# 01-LED.net
KiCad netlist of a schematic drawn in Altium Designer
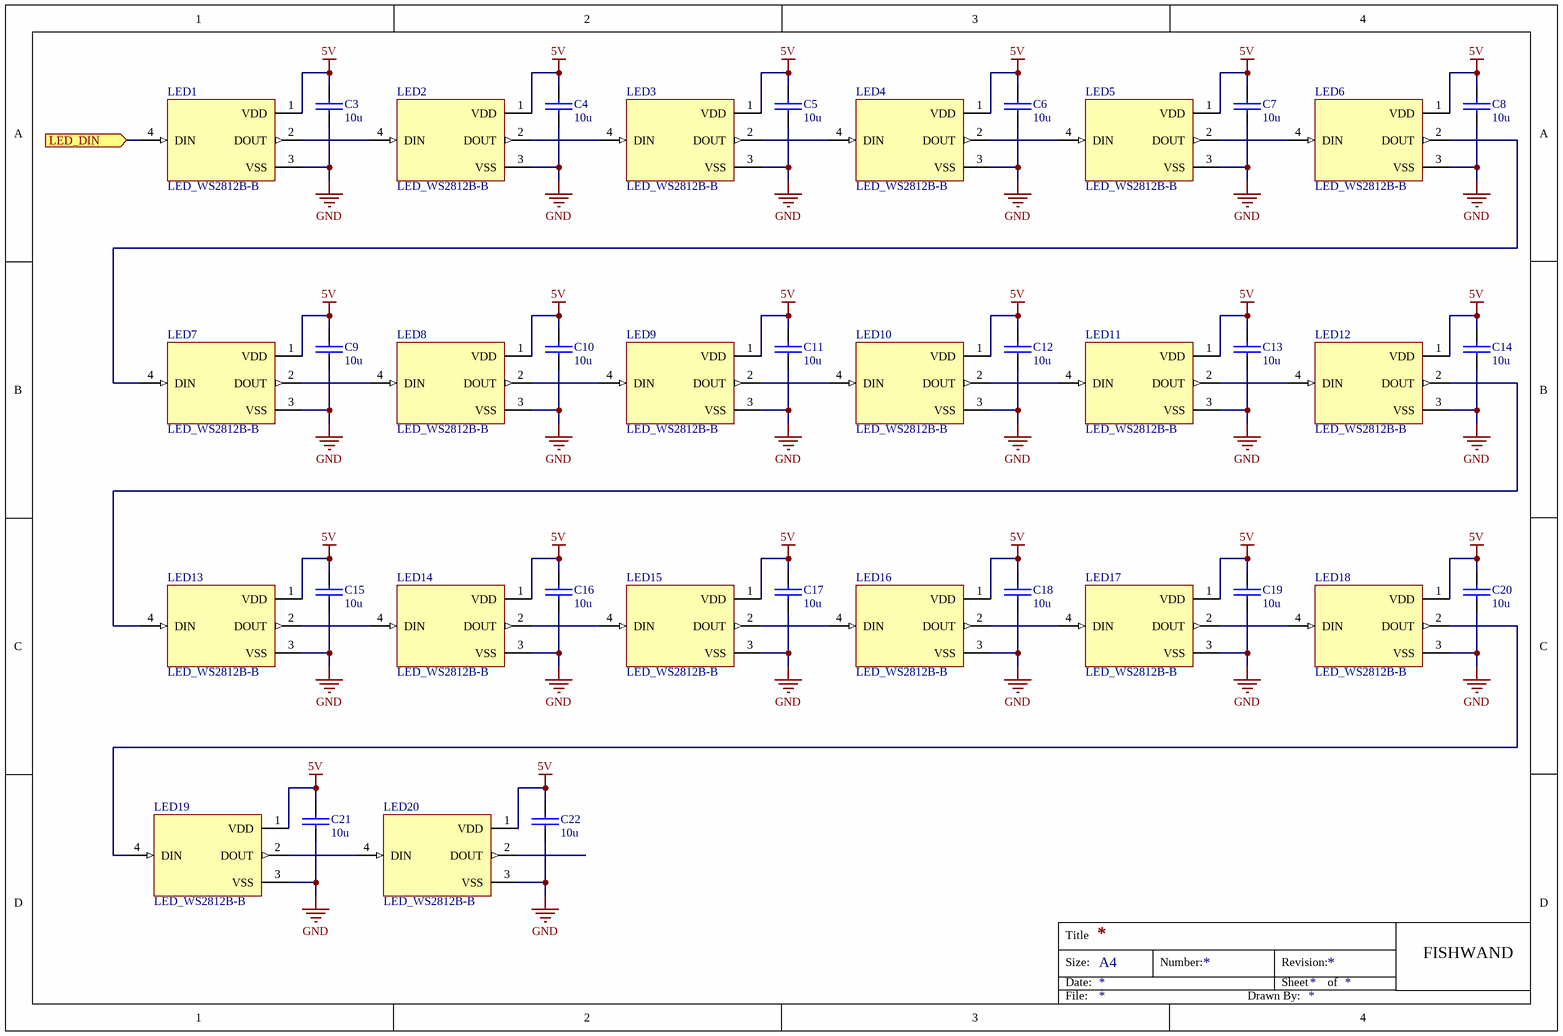
[diagram p0: 01-LED.SchDoc]

(export (version "E")
  (design (tool "Eeschema 10.0.6"))
  (components
    (comp (ref "C3")
      (value "10u")
      (footprint "CAPC100X50X65")
      (description "CAP CER 10UF 10V X5R 0402")
      (fields (field (name "MANUFACTURER") "Samsung Electro-Mechanics"))
      (libsource (lib "FishWand_Schlib") (part "C_10UF_10V_X5R_0402"))
    )
    (comp (ref "C4")
      (value "10u")
      (footprint "CAPC100X50X65")
      (description "CAP CER 10UF 10V X5R 0402")
      (fields (field (name "MANUFACTURER") "Samsung Electro-Mechanics"))
      (libsource (lib "FishWand_Schlib") (part "C_10UF_10V_X5R_0402"))
    )
    (comp (ref "C5")
      (value "10u")
      (footprint "CAPC100X50X65")
      (description "CAP CER 10UF 10V X5R 0402")
      (fields (field (name "MANUFACTURER") "Samsung Electro-Mechanics"))
      (libsource (lib "FishWand_Schlib") (part "C_10UF_10V_X5R_0402"))
    )
    (comp (ref "C6")
      (value "10u")
      (footprint "CAPC100X50X65")
      (description "CAP CER 10UF 10V X5R 0402")
      (fields (field (name "MANUFACTURER") "Samsung Electro-Mechanics"))
      (libsource (lib "FishWand_Schlib") (part "C_10UF_10V_X5R_0402"))
    )
    (comp (ref "C7")
      (value "10u")
      (footprint "CAPC100X50X65")
      (description "CAP CER 10UF 10V X5R 0402")
      (fields (field (name "MANUFACTURER") "Samsung Electro-Mechanics"))
      (libsource (lib "FishWand_Schlib") (part "C_10UF_10V_X5R_0402"))
    )
    (comp (ref "C8")
      (value "10u")
      (footprint "CAPC100X50X65")
      (description "CAP CER 10UF 10V X5R 0402")
      (fields (field (name "MANUFACTURER") "Samsung Electro-Mechanics"))
      (libsource (lib "FishWand_Schlib") (part "C_10UF_10V_X5R_0402"))
    )
    (comp (ref "C9")
      (value "10u")
      (footprint "CAPC100X50X65")
      (description "CAP CER 10UF 10V X5R 0402")
      (fields (field (name "MANUFACTURER") "Samsung Electro-Mechanics"))
      (libsource (lib "FishWand_Schlib") (part "C_10UF_10V_X5R_0402"))
    )
    (comp (ref "C10")
      (value "10u")
      (footprint "CAPC100X50X65")
      (description "CAP CER 10UF 10V X5R 0402")
      (fields (field (name "MANUFACTURER") "Samsung Electro-Mechanics"))
      (libsource (lib "FishWand_Schlib") (part "C_10UF_10V_X5R_0402"))
    )
    (comp (ref "C11")
      (value "10u")
      (footprint "CAPC100X50X65")
      (description "CAP CER 10UF 10V X5R 0402")
      (fields (field (name "MANUFACTURER") "Samsung Electro-Mechanics"))
      (libsource (lib "FishWand_Schlib") (part "C_10UF_10V_X5R_0402"))
    )
    (comp (ref "C12")
      (value "10u")
      (footprint "CAPC100X50X65")
      (description "CAP CER 10UF 10V X5R 0402")
      (fields (field (name "MANUFACTURER") "Samsung Electro-Mechanics"))
      (libsource (lib "FishWand_Schlib") (part "C_10UF_10V_X5R_0402"))
    )
    (comp (ref "C13")
      (value "10u")
      (footprint "CAPC100X50X65")
      (description "CAP CER 10UF 10V X5R 0402")
      (fields (field (name "MANUFACTURER") "Samsung Electro-Mechanics"))
      (libsource (lib "FishWand_Schlib") (part "C_10UF_10V_X5R_0402"))
    )
    (comp (ref "C14")
      (value "10u")
      (footprint "CAPC100X50X65")
      (description "CAP CER 10UF 10V X5R 0402")
      (fields (field (name "MANUFACTURER") "Samsung Electro-Mechanics"))
      (libsource (lib "FishWand_Schlib") (part "C_10UF_10V_X5R_0402"))
    )
    (comp (ref "C15")
      (value "10u")
      (footprint "CAPC100X50X65")
      (description "CAP CER 10UF 10V X5R 0402")
      (fields (field (name "MANUFACTURER") "Samsung Electro-Mechanics"))
      (libsource (lib "FishWand_Schlib") (part "C_10UF_10V_X5R_0402"))
    )
    (comp (ref "C16")
      (value "10u")
      (footprint "CAPC100X50X65")
      (description "CAP CER 10UF 10V X5R 0402")
      (fields (field (name "MANUFACTURER") "Samsung Electro-Mechanics"))
      (libsource (lib "FishWand_Schlib") (part "C_10UF_10V_X5R_0402"))
    )
    (comp (ref "C17")
      (value "10u")
      (footprint "CAPC100X50X65")
      (description "CAP CER 10UF 10V X5R 0402")
      (fields (field (name "MANUFACTURER") "Samsung Electro-Mechanics"))
      (libsource (lib "FishWand_Schlib") (part "C_10UF_10V_X5R_0402"))
    )
    (comp (ref "C18")
      (value "10u")
      (footprint "CAPC100X50X65")
      (description "CAP CER 10UF 10V X5R 0402")
      (fields (field (name "MANUFACTURER") "Samsung Electro-Mechanics"))
      (libsource (lib "FishWand_Schlib") (part "C_10UF_10V_X5R_0402"))
    )
    (comp (ref "C19")
      (value "10u")
      (footprint "CAPC100X50X65")
      (description "CAP CER 10UF 10V X5R 0402")
      (fields (field (name "MANUFACTURER") "Samsung Electro-Mechanics"))
      (libsource (lib "FishWand_Schlib") (part "C_10UF_10V_X5R_0402"))
    )
    (comp (ref "C20")
      (value "10u")
      (footprint "CAPC100X50X65")
      (description "CAP CER 10UF 10V X5R 0402")
      (fields (field (name "MANUFACTURER") "Samsung Electro-Mechanics"))
      (libsource (lib "FishWand_Schlib") (part "C_10UF_10V_X5R_0402"))
    )
    (comp (ref "C21")
      (value "10u")
      (footprint "CAPC100X50X65")
      (description "CAP CER 10UF 10V X5R 0402")
      (fields (field (name "MANUFACTURER") "Samsung Electro-Mechanics"))
      (libsource (lib "FishWand_Schlib") (part "C_10UF_10V_X5R_0402"))
    )
    (comp (ref "C22")
      (value "10u")
      (footprint "CAPC100X50X65")
      (description "CAP CER 10UF 10V X5R 0402")
      (fields (field (name "MANUFACTURER") "Samsung Electro-Mechanics"))
      (libsource (lib "FishWand_Schlib") (part "C_10UF_10V_X5R_0402"))
    )
    (comp (ref "LED1")
      (value "LED_WS2812B-B")
      (footprint "LED_WS2812B-B")
      (description "Intelligent control LED integrated light source")
      (fields (field (name "MANUFACTURER") "Worldsemi"))
      (libsource (lib "FishWand_Schlib") (part "LED_WS2812B-B"))
    )
    (comp (ref "LED2")
      (value "LED_WS2812B-B")
      (footprint "LED_WS2812B-B")
      (description "Intelligent control LED integrated light source")
      (fields (field (name "MANUFACTURER") "Worldsemi"))
      (libsource (lib "FishWand_Schlib") (part "LED_WS2812B-B"))
    )
    (comp (ref "LED3")
      (value "LED_WS2812B-B")
      (footprint "LED_WS2812B-B")
      (description "Intelligent control LED integrated light source")
      (fields (field (name "MANUFACTURER") "Worldsemi"))
      (libsource (lib "FishWand_Schlib") (part "LED_WS2812B-B"))
    )
    (comp (ref "LED4")
      (value "LED_WS2812B-B")
      (footprint "LED_WS2812B-B")
      (description "Intelligent control LED integrated light source")
      (fields (field (name "MANUFACTURER") "Worldsemi"))
      (libsource (lib "FishWand_Schlib") (part "LED_WS2812B-B"))
    )
    (comp (ref "LED5")
      (value "LED_WS2812B-B")
      (footprint "LED_WS2812B-B")
      (description "Intelligent control LED integrated light source")
      (fields (field (name "MANUFACTURER") "Worldsemi"))
      (libsource (lib "FishWand_Schlib") (part "LED_WS2812B-B"))
    )
    (comp (ref "LED6")
      (value "LED_WS2812B-B")
      (footprint "LED_WS2812B-B")
      (description "Intelligent control LED integrated light source")
      (fields (field (name "MANUFACTURER") "Worldsemi"))
      (libsource (lib "FishWand_Schlib") (part "LED_WS2812B-B"))
    )
    (comp (ref "LED7")
      (value "LED_WS2812B-B")
      (footprint "LED_WS2812B-B")
      (description "Intelligent control LED integrated light source")
      (fields (field (name "MANUFACTURER") "Worldsemi"))
      (libsource (lib "FishWand_Schlib") (part "LED_WS2812B-B"))
    )
    (comp (ref "LED8")
      (value "LED_WS2812B-B")
      (footprint "LED_WS2812B-B")
      (description "Intelligent control LED integrated light source")
      (fields (field (name "MANUFACTURER") "Worldsemi"))
      (libsource (lib "FishWand_Schlib") (part "LED_WS2812B-B"))
    )
    (comp (ref "LED9")
      (value "LED_WS2812B-B")
      (footprint "LED_WS2812B-B")
      (description "Intelligent control LED integrated light source")
      (fields (field (name "MANUFACTURER") "Worldsemi"))
      (libsource (lib "FishWand_Schlib") (part "LED_WS2812B-B"))
    )
    (comp (ref "LED10")
      (value "LED_WS2812B-B")
      (footprint "LED_WS2812B-B")
      (description "Intelligent control LED integrated light source")
      (fields (field (name "MANUFACTURER") "Worldsemi"))
      (libsource (lib "FishWand_Schlib") (part "LED_WS2812B-B"))
    )
    (comp (ref "LED11")
      (value "LED_WS2812B-B")
      (footprint "LED_WS2812B-B")
      (description "Intelligent control LED integrated light source")
      (fields (field (name "MANUFACTURER") "Worldsemi"))
      (libsource (lib "FishWand_Schlib") (part "LED_WS2812B-B"))
    )
    (comp (ref "LED12")
      (value "LED_WS2812B-B")
      (footprint "LED_WS2812B-B")
      (description "Intelligent control LED integrated light source")
      (fields (field (name "MANUFACTURER") "Worldsemi"))
      (libsource (lib "FishWand_Schlib") (part "LED_WS2812B-B"))
    )
    (comp (ref "LED13")
      (value "LED_WS2812B-B")
      (footprint "LED_WS2812B-B")
      (description "Intelligent control LED integrated light source")
      (fields (field (name "MANUFACTURER") "Worldsemi"))
      (libsource (lib "FishWand_Schlib") (part "LED_WS2812B-B"))
    )
    (comp (ref "LED14")
      (value "LED_WS2812B-B")
      (footprint "LED_WS2812B-B")
      (description "Intelligent control LED integrated light source")
      (fields (field (name "MANUFACTURER") "Worldsemi"))
      (libsource (lib "FishWand_Schlib") (part "LED_WS2812B-B"))
    )
    (comp (ref "LED15")
      (value "LED_WS2812B-B")
      (footprint "LED_WS2812B-B")
      (description "Intelligent control LED integrated light source")
      (fields (field (name "MANUFACTURER") "Worldsemi"))
      (libsource (lib "FishWand_Schlib") (part "LED_WS2812B-B"))
    )
    (comp (ref "LED16")
      (value "LED_WS2812B-B")
      (footprint "LED_WS2812B-B")
      (description "Intelligent control LED integrated light source")
      (fields (field (name "MANUFACTURER") "Worldsemi"))
      (libsource (lib "FishWand_Schlib") (part "LED_WS2812B-B"))
    )
    (comp (ref "LED17")
      (value "LED_WS2812B-B")
      (footprint "LED_WS2812B-B")
      (description "Intelligent control LED integrated light source")
      (fields (field (name "MANUFACTURER") "Worldsemi"))
      (libsource (lib "FishWand_Schlib") (part "LED_WS2812B-B"))
    )
    (comp (ref "LED18")
      (value "LED_WS2812B-B")
      (footprint "LED_WS2812B-B")
      (description "Intelligent control LED integrated light source")
      (fields (field (name "MANUFACTURER") "Worldsemi"))
      (libsource (lib "FishWand_Schlib") (part "LED_WS2812B-B"))
    )
    (comp (ref "LED19")
      (value "LED_WS2812B-B")
      (footprint "LED_WS2812B-B")
      (description "Intelligent control LED integrated light source")
      (fields (field (name "MANUFACTURER") "Worldsemi"))
      (libsource (lib "FishWand_Schlib") (part "LED_WS2812B-B"))
    )
    (comp (ref "LED20")
      (value "LED_WS2812B-B")
      (footprint "LED_WS2812B-B")
      (description "Intelligent control LED integrated light source")
      (fields (field (name "MANUFACTURER") "Worldsemi"))
      (libsource (lib "FishWand_Schlib") (part "LED_WS2812B-B"))
    )
  )
  (nets
    (net (code "1") (name "/LED_DIN") (class "Default")
      (node (ref "LED1") (pin "4") (pinfunction "DIN_4") (pintype "input"))
    )
    (net (code "2") (name "5V") (class "Default")
      (node (ref "C10") (pin "1") (pinfunction "1_1") (pintype "passive"))
      (node (ref "C11") (pin "1") (pinfunction "1_1") (pintype "passive"))
      (node (ref "C12") (pin "1") (pinfunction "1_1") (pintype "passive"))
      (node (ref "C13") (pin "1") (pinfunction "1_1") (pintype "passive"))
      (node (ref "C14") (pin "1") (pinfunction "1_1") (pintype "passive"))
      (node (ref "C15") (pin "1") (pinfunction "1_1") (pintype "passive"))
      (node (ref "C16") (pin "1") (pinfunction "1_1") (pintype "passive"))
      (node (ref "C17") (pin "1") (pinfunction "1_1") (pintype "passive"))
      (node (ref "C18") (pin "1") (pinfunction "1_1") (pintype "passive"))
      (node (ref "C19") (pin "1") (pinfunction "1_1") (pintype "passive"))
      (node (ref "C20") (pin "1") (pinfunction "1_1") (pintype "passive"))
      (node (ref "C21") (pin "1") (pinfunction "1_1") (pintype "passive"))
      (node (ref "C22") (pin "1") (pinfunction "1_1") (pintype "passive"))
      (node (ref "C3") (pin "1") (pinfunction "1_1") (pintype "passive"))
      (node (ref "C4") (pin "1") (pinfunction "1_1") (pintype "passive"))
      (node (ref "C5") (pin "1") (pinfunction "1_1") (pintype "passive"))
      (node (ref "C6") (pin "1") (pinfunction "1_1") (pintype "passive"))
      (node (ref "C7") (pin "1") (pinfunction "1_1") (pintype "passive"))
      (node (ref "C8") (pin "1") (pinfunction "1_1") (pintype "passive"))
      (node (ref "C9") (pin "1") (pinfunction "1_1") (pintype "passive"))
      (node (ref "LED1") (pin "1") (pinfunction "VDD_1") (pintype "power_in"))
      (node (ref "LED10") (pin "1") (pinfunction "VDD_1") (pintype "power_in"))
      (node (ref "LED11") (pin "1") (pinfunction "VDD_1") (pintype "power_in"))
      (node (ref "LED12") (pin "1") (pinfunction "VDD_1") (pintype "power_in"))
      (node (ref "LED13") (pin "1") (pinfunction "VDD_1") (pintype "power_in"))
      (node (ref "LED14") (pin "1") (pinfunction "VDD_1") (pintype "power_in"))
      (node (ref "LED15") (pin "1") (pinfunction "VDD_1") (pintype "power_in"))
      (node (ref "LED16") (pin "1") (pinfunction "VDD_1") (pintype "power_in"))
      (node (ref "LED17") (pin "1") (pinfunction "VDD_1") (pintype "power_in"))
      (node (ref "LED18") (pin "1") (pinfunction "VDD_1") (pintype "power_in"))
      (node (ref "LED19") (pin "1") (pinfunction "VDD_1") (pintype "power_in"))
      (node (ref "LED2") (pin "1") (pinfunction "VDD_1") (pintype "power_in"))
      (node (ref "LED20") (pin "1") (pinfunction "VDD_1") (pintype "power_in"))
      (node (ref "LED3") (pin "1") (pinfunction "VDD_1") (pintype "power_in"))
      (node (ref "LED4") (pin "1") (pinfunction "VDD_1") (pintype "power_in"))
      (node (ref "LED5") (pin "1") (pinfunction "VDD_1") (pintype "power_in"))
      (node (ref "LED6") (pin "1") (pinfunction "VDD_1") (pintype "power_in"))
      (node (ref "LED7") (pin "1") (pinfunction "VDD_1") (pintype "power_in"))
      (node (ref "LED8") (pin "1") (pinfunction "VDD_1") (pintype "power_in"))
      (node (ref "LED9") (pin "1") (pinfunction "VDD_1") (pintype "power_in"))
    )
    (net (code "3") (name "GND") (class "Default")
      (node (ref "C10") (pin "2") (pinfunction "2_2") (pintype "passive"))
      (node (ref "C11") (pin "2") (pinfunction "2_2") (pintype "passive"))
      (node (ref "C12") (pin "2") (pinfunction "2_2") (pintype "passive"))
      (node (ref "C13") (pin "2") (pinfunction "2_2") (pintype "passive"))
      (node (ref "C14") (pin "2") (pinfunction "2_2") (pintype "passive"))
      (node (ref "C15") (pin "2") (pinfunction "2_2") (pintype "passive"))
      (node (ref "C16") (pin "2") (pinfunction "2_2") (pintype "passive"))
      (node (ref "C17") (pin "2") (pinfunction "2_2") (pintype "passive"))
      (node (ref "C18") (pin "2") (pinfunction "2_2") (pintype "passive"))
      (node (ref "C19") (pin "2") (pinfunction "2_2") (pintype "passive"))
      (node (ref "C20") (pin "2") (pinfunction "2_2") (pintype "passive"))
      (node (ref "C21") (pin "2") (pinfunction "2_2") (pintype "passive"))
      (node (ref "C22") (pin "2") (pinfunction "2_2") (pintype "passive"))
      (node (ref "C3") (pin "2") (pinfunction "2_2") (pintype "passive"))
      (node (ref "C4") (pin "2") (pinfunction "2_2") (pintype "passive"))
      (node (ref "C5") (pin "2") (pinfunction "2_2") (pintype "passive"))
      (node (ref "C6") (pin "2") (pinfunction "2_2") (pintype "passive"))
      (node (ref "C7") (pin "2") (pinfunction "2_2") (pintype "passive"))
      (node (ref "C8") (pin "2") (pinfunction "2_2") (pintype "passive"))
      (node (ref "C9") (pin "2") (pinfunction "2_2") (pintype "passive"))
      (node (ref "LED1") (pin "3") (pinfunction "VSS_3") (pintype "power_in"))
      (node (ref "LED10") (pin "3") (pinfunction "VSS_3") (pintype "power_in"))
      (node (ref "LED11") (pin "3") (pinfunction "VSS_3") (pintype "power_in"))
      (node (ref "LED12") (pin "3") (pinfunction "VSS_3") (pintype "power_in"))
      (node (ref "LED13") (pin "3") (pinfunction "VSS_3") (pintype "power_in"))
      (node (ref "LED14") (pin "3") (pinfunction "VSS_3") (pintype "power_in"))
      (node (ref "LED15") (pin "3") (pinfunction "VSS_3") (pintype "power_in"))
      (node (ref "LED16") (pin "3") (pinfunction "VSS_3") (pintype "power_in"))
      (node (ref "LED17") (pin "3") (pinfunction "VSS_3") (pintype "power_in"))
      (node (ref "LED18") (pin "3") (pinfunction "VSS_3") (pintype "power_in"))
      (node (ref "LED19") (pin "3") (pinfunction "VSS_3") (pintype "power_in"))
      (node (ref "LED2") (pin "3") (pinfunction "VSS_3") (pintype "power_in"))
      (node (ref "LED20") (pin "3") (pinfunction "VSS_3") (pintype "power_in"))
      (node (ref "LED3") (pin "3") (pinfunction "VSS_3") (pintype "power_in"))
      (node (ref "LED4") (pin "3") (pinfunction "VSS_3") (pintype "power_in"))
      (node (ref "LED5") (pin "3") (pinfunction "VSS_3") (pintype "power_in"))
      (node (ref "LED6") (pin "3") (pinfunction "VSS_3") (pintype "power_in"))
      (node (ref "LED7") (pin "3") (pinfunction "VSS_3") (pintype "power_in"))
      (node (ref "LED8") (pin "3") (pinfunction "VSS_3") (pintype "power_in"))
      (node (ref "LED9") (pin "3") (pinfunction "VSS_3") (pintype "power_in"))
    )
    (net (code "4") (name "Net-(LED1-DOUT)") (class "Default")
      (node (ref "LED1") (pin "2") (pinfunction "DOUT_2") (pintype "output"))
      (node (ref "LED2") (pin "4") (pinfunction "DIN_4") (pintype "input"))
    )
    (net (code "5") (name "Net-(LED2-DOUT)") (class "Default")
      (node (ref "LED2") (pin "2") (pinfunction "DOUT_2") (pintype "output"))
      (node (ref "LED3") (pin "4") (pinfunction "DIN_4") (pintype "input"))
    )
    (net (code "6") (name "Net-(LED3-DOUT)") (class "Default")
      (node (ref "LED3") (pin "2") (pinfunction "DOUT_2") (pintype "output"))
      (node (ref "LED4") (pin "4") (pinfunction "DIN_4") (pintype "input"))
    )
    (net (code "7") (name "Net-(LED4-DOUT)") (class "Default")
      (node (ref "LED4") (pin "2") (pinfunction "DOUT_2") (pintype "output"))
      (node (ref "LED5") (pin "4") (pinfunction "DIN_4") (pintype "input"))
    )
    (net (code "8") (name "Net-(LED5-DOUT)") (class "Default")
      (node (ref "LED5") (pin "2") (pinfunction "DOUT_2") (pintype "output"))
      (node (ref "LED6") (pin "4") (pinfunction "DIN_4") (pintype "input"))
    )
    (net (code "9") (name "Net-(LED6-DOUT)") (class "Default")
      (node (ref "LED6") (pin "2") (pinfunction "DOUT_2") (pintype "output"))
      (node (ref "LED7") (pin "4") (pinfunction "DIN_4") (pintype "input"))
    )
    (net (code "10") (name "Net-(LED7-DOUT)") (class "Default")
      (node (ref "LED7") (pin "2") (pinfunction "DOUT_2") (pintype "output"))
      (node (ref "LED8") (pin "4") (pinfunction "DIN_4") (pintype "input"))
    )
    (net (code "11") (name "Net-(LED8-DOUT)") (class "Default")
      (node (ref "LED8") (pin "2") (pinfunction "DOUT_2") (pintype "output"))
      (node (ref "LED9") (pin "4") (pinfunction "DIN_4") (pintype "input"))
    )
    (net (code "12") (name "Net-(LED10-DIN)") (class "Default")
      (node (ref "LED10") (pin "4") (pinfunction "DIN_4") (pintype "input"))
      (node (ref "LED9") (pin "2") (pinfunction "DOUT_2") (pintype "output"))
    )
    (net (code "13") (name "Net-(LED10-DOUT)") (class "Default")
      (node (ref "LED10") (pin "2") (pinfunction "DOUT_2") (pintype "output"))
      (node (ref "LED11") (pin "4") (pinfunction "DIN_4") (pintype "input"))
    )
    (net (code "14") (name "Net-(LED11-DOUT)") (class "Default")
      (node (ref "LED11") (pin "2") (pinfunction "DOUT_2") (pintype "output"))
      (node (ref "LED12") (pin "4") (pinfunction "DIN_4") (pintype "input"))
    )
    (net (code "15") (name "Net-(LED12-DOUT)") (class "Default")
      (node (ref "LED12") (pin "2") (pinfunction "DOUT_2") (pintype "output"))
      (node (ref "LED13") (pin "4") (pinfunction "DIN_4") (pintype "input"))
    )
    (net (code "16") (name "Net-(LED13-DOUT)") (class "Default")
      (node (ref "LED13") (pin "2") (pinfunction "DOUT_2") (pintype "output"))
      (node (ref "LED14") (pin "4") (pinfunction "DIN_4") (pintype "input"))
    )
    (net (code "17") (name "Net-(LED14-DOUT)") (class "Default")
      (node (ref "LED14") (pin "2") (pinfunction "DOUT_2") (pintype "output"))
      (node (ref "LED15") (pin "4") (pinfunction "DIN_4") (pintype "input"))
    )
    (net (code "18") (name "Net-(LED15-DOUT)") (class "Default")
      (node (ref "LED15") (pin "2") (pinfunction "DOUT_2") (pintype "output"))
      (node (ref "LED16") (pin "4") (pinfunction "DIN_4") (pintype "input"))
    )
    (net (code "19") (name "Net-(LED16-DOUT)") (class "Default")
      (node (ref "LED16") (pin "2") (pinfunction "DOUT_2") (pintype "output"))
      (node (ref "LED17") (pin "4") (pinfunction "DIN_4") (pintype "input"))
    )
    (net (code "20") (name "Net-(LED17-DOUT)") (class "Default")
      (node (ref "LED17") (pin "2") (pinfunction "DOUT_2") (pintype "output"))
      (node (ref "LED18") (pin "4") (pinfunction "DIN_4") (pintype "input"))
    )
    (net (code "21") (name "Net-(LED18-DOUT)") (class "Default")
      (node (ref "LED18") (pin "2") (pinfunction "DOUT_2") (pintype "output"))
      (node (ref "LED19") (pin "4") (pinfunction "DIN_4") (pintype "input"))
    )
    (net (code "22") (name "Net-(LED19-DOUT)") (class "Default")
      (node (ref "LED19") (pin "2") (pinfunction "DOUT_2") (pintype "output"))
      (node (ref "LED20") (pin "4") (pinfunction "DIN_4") (pintype "input"))
    )
    (net (code "23") (name "unconnected-(LED20-DOUT-Pad2)") (class "Default")
      (node (ref "LED20") (pin "2") (pinfunction "DOUT_2") (pintype "output"))
    )
  )
)
